# 3_3V_Regulator.net
KiCad netlist of a schematic drawn in Altium Designer
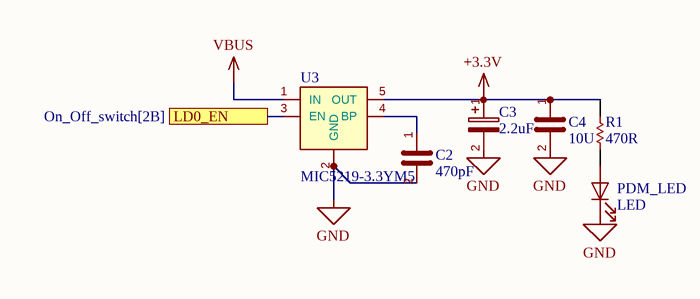
[diagram p0: 3.3V_Regulator.SchDoc]

(export (version "E")
  (design (tool "Eeschema 10.0.6"))
  (components
    (comp (ref "C2")
      (value "470pF")
      (footprint "CAPC2013X70X45NL10T25")
      (libsource (lib "Thermal_Camera") (part "C"))
    )
    (comp (ref "C3")
      (value "2.2uF")
      (footprint "Elco capacitor")
      (libsource (lib "Thermal_Camera") (part "C_Polarized"))
    )
    (comp (ref "C4")
      (value "10U")
      (footprint "CAPC2013X70X45NL10T25")
      (libsource (lib "Thermal_Camera") (part "C"))
    )
    (comp (ref "PDM_LED")
      (value "LED")
      (footprint "LEDC2012X70N")
      (libsource (lib "Thermal_Camera") (part "LED"))
    )
    (comp (ref "R1")
      (value "470R")
      (footprint "RESC2013X70X40NL20T20")
      (description "Chip Resistor, 1 KOhm, +/- 1%, 125 mW, -55 to 155 degC, 0805 (2012 Metric), RoHS, Tape and Reel")
      (fields (field (name "TOLERANCE") "1%") (field (name "MANUFACTURER") "Yageo"))
      (libsource (lib "Thermal_Camera") (part "CMP-2100-03671-1"))
    )
    (comp (ref "U3")
      (value "MIC5219-3.3YM5")
      (footprint "FP-SOT23-5LD-PL-1-MFG")
      (libsource (lib "Thermal_Camera") (part "MIC5219-3.3YM5"))
    )
  )
  (nets
    (net (code "1") (name "+3.3V") (class "Default")
      (node (ref "C3") (pin "1") (pinfunction "1_1") (pintype "passive"))
      (node (ref "C4") (pin "1") (pinfunction "1_1") (pintype "passive"))
      (node (ref "R1") (pin "1") (pinfunction "1_1") (pintype "passive"))
      (node (ref "U3") (pin "5") (pinfunction "OUT_5") (pintype "passive"))
    )
    (net (code "2") (name "/LD0_EN") (class "Default")
      (node (ref "U3") (pin "3") (pinfunction "EN_3") (pintype "passive"))
    )
    (net (code "3") (name "GND") (class "Default")
      (node (ref "C2") (pin "2") (pinfunction "2_2") (pintype "passive"))
      (node (ref "C3") (pin "2") (pinfunction "2_2") (pintype "passive"))
      (node (ref "C4") (pin "2") (pinfunction "2_2") (pintype "passive"))
      (node (ref "PDM_LED") (pin "C") (pinfunction "1_C") (pintype "passive"))
      (node (ref "U3") (pin "2") (pinfunction "GND_2") (pintype "passive"))
    )
    (net (code "4") (name "Net-(PDM_LED-2)") (class "Default")
      (node (ref "PDM_LED") (pin "A") (pinfunction "2_A") (pintype "passive"))
      (node (ref "R1") (pin "2") (pinfunction "2_2") (pintype "passive"))
    )
    (net (code "5") (name "Net-(U3-BP)") (class "Default")
      (node (ref "C2") (pin "1") (pinfunction "1_1") (pintype "passive"))
      (node (ref "U3") (pin "4") (pinfunction "BP_4") (pintype "passive"))
    )
    (net (code "6") (name "VBUS") (class "Default")
      (node (ref "U3") (pin "1") (pinfunction "IN_1") (pintype "passive"))
    )
  )
)
